# 0028.net
KiCad netlist of a schematic drawn in Altium Designer
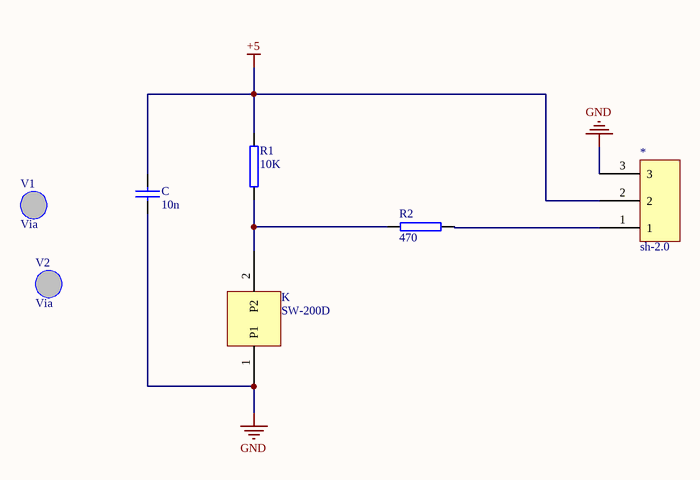
[diagram p0: 0028.SchDoc]

(export (version "E")
  (design (tool "Eeschema 10.0.6"))
  (components
    (comp (ref "*") (value "sh-2.0") (footprint "sh-2.0") (libsource (lib "zhangchong") (part "sh-2.0")))
    (comp (ref "C") (value "10n") (footprint "0402") (libsource (lib "gupeng_sch") (part "CAP0402")))
    (comp (ref "K") (value "SW-200D") (footprint "SW-200D") (libsource (lib "zhangchong") (part "SW-200D")))
    (comp (ref "R1") (value "10K") (footprint "0402") (libsource (lib "gupeng_sch") (part "RES0402")))
    (comp (ref "R2") (value "470") (footprint "0402") (libsource (lib "gupeng_sch") (part "RES0402")))
    (comp (ref "V1") (value "Via") (footprint "zhaoyujiu:Via") (libsource (lib "zhaoyujiu") (part "Via")))
    (comp (ref "V2") (value "Via") (footprint "zhaoyujiu:Via") (libsource (lib "zhaoyujiu") (part "Via")))
  )
  (nets
    (net (code "1") (name "+5") (class "Default")
      (node (ref "*") (pin "2") (pinfunction "2_2") (pintype "passive"))
      (node (ref "C") (pin "1") (pinfunction "1_1") (pintype "passive"))
      (node (ref "R1") (pin "2") (pinfunction "2_2") (pintype "passive"))
    )
    (net (code "2") (name "GND") (class "Default")
      (node (ref "*") (pin "3") (pinfunction "3_3") (pintype "passive"))
      (node (ref "C") (pin "2") (pinfunction "2_2") (pintype "passive"))
      (node (ref "K") (pin "1") (pinfunction "P1_1") (pintype "passive"))
    )
    (net (code "3") (name "Net-(*-Pad1)") (class "Default")
      (node (ref "*") (pin "1") (pinfunction "1_1") (pintype "passive"))
      (node (ref "R2") (pin "2") (pinfunction "2_2") (pintype "passive"))
    )
    (net (code "4") (name "Net-(K-P2)") (class "Default")
      (node (ref "K") (pin "2") (pinfunction "P2_2") (pintype "passive"))
      (node (ref "R1") (pin "1") (pinfunction "1_1") (pintype "passive"))
      (node (ref "R2") (pin "1") (pinfunction "1_1") (pintype "passive"))
    )
  )
)
